# StereoscopicPi.net
KiCad netlist of a schematic drawn in Altium Designer
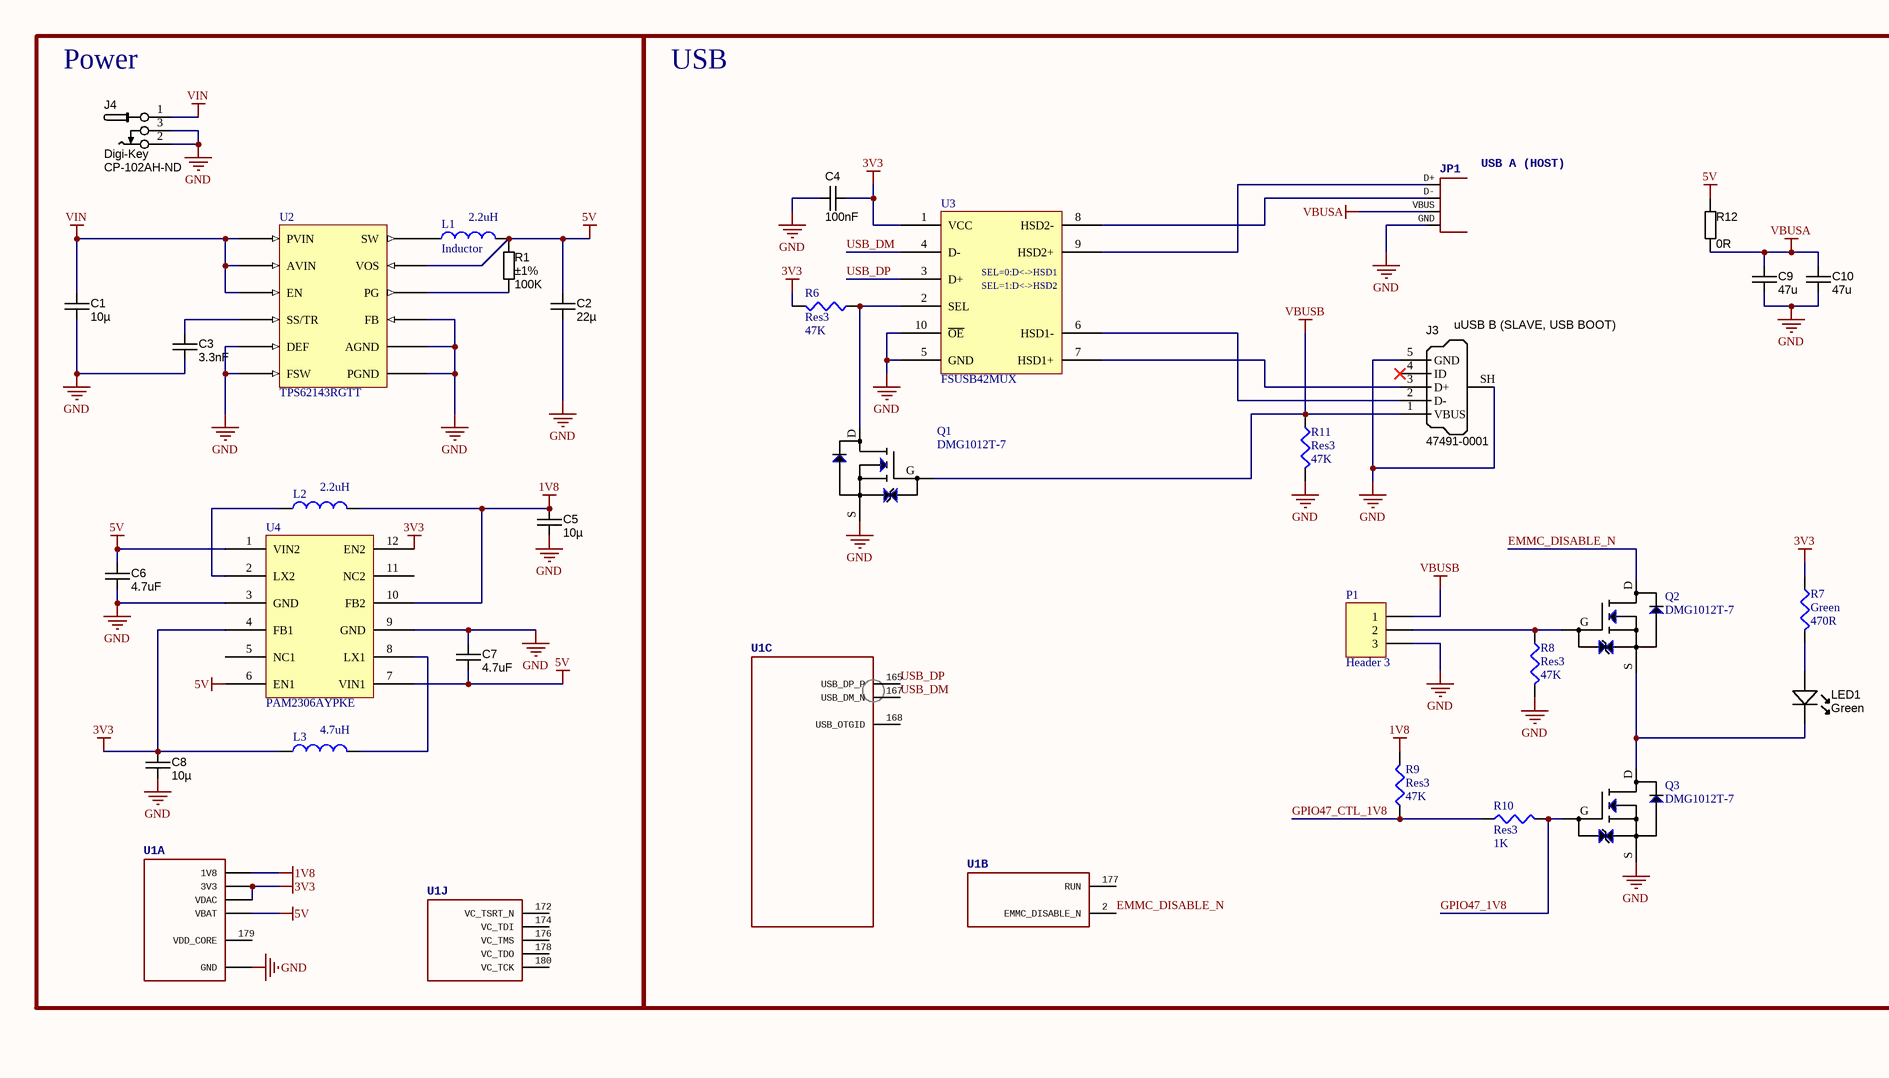
[diagram p0: StereoscopicPi.SchDoc, top left]
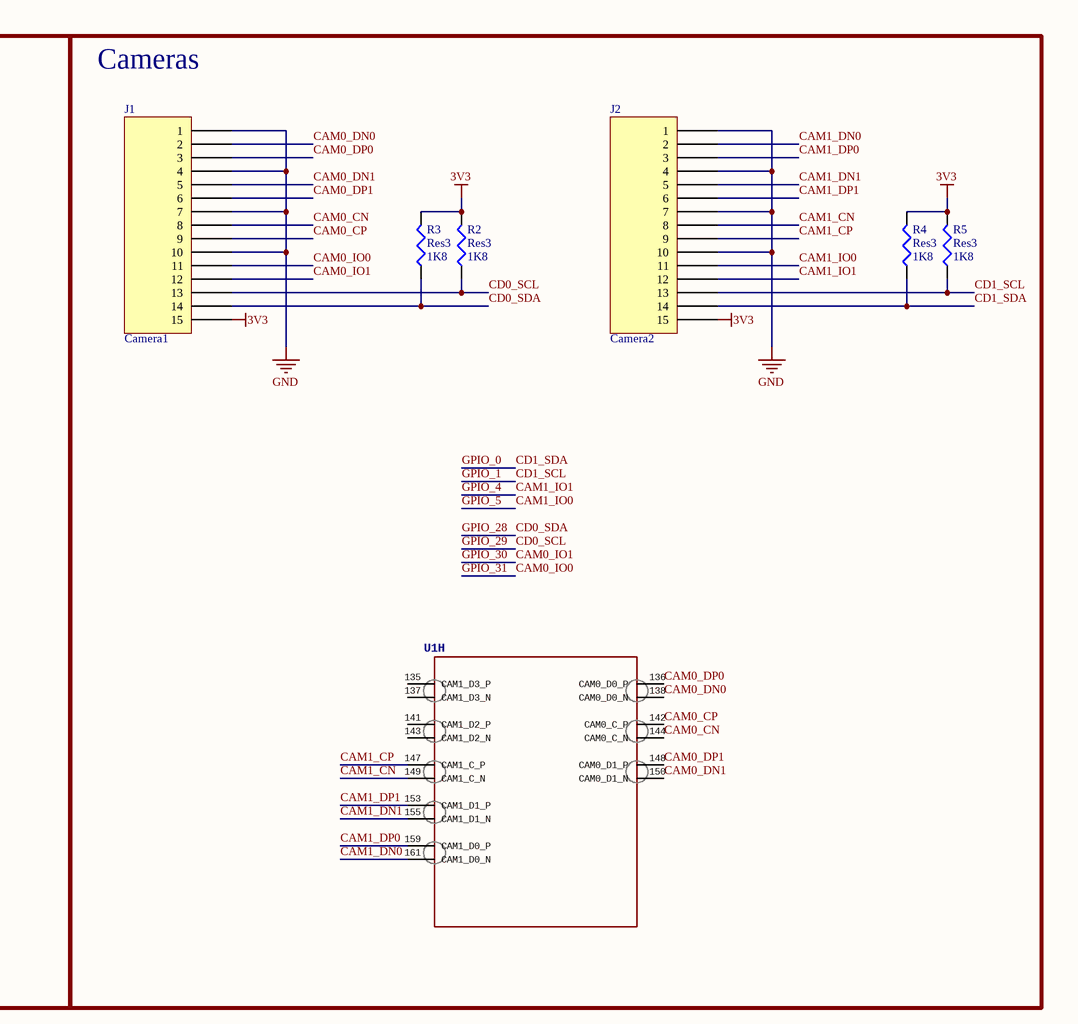
[diagram p1: StereoscopicPi.SchDoc, top right]
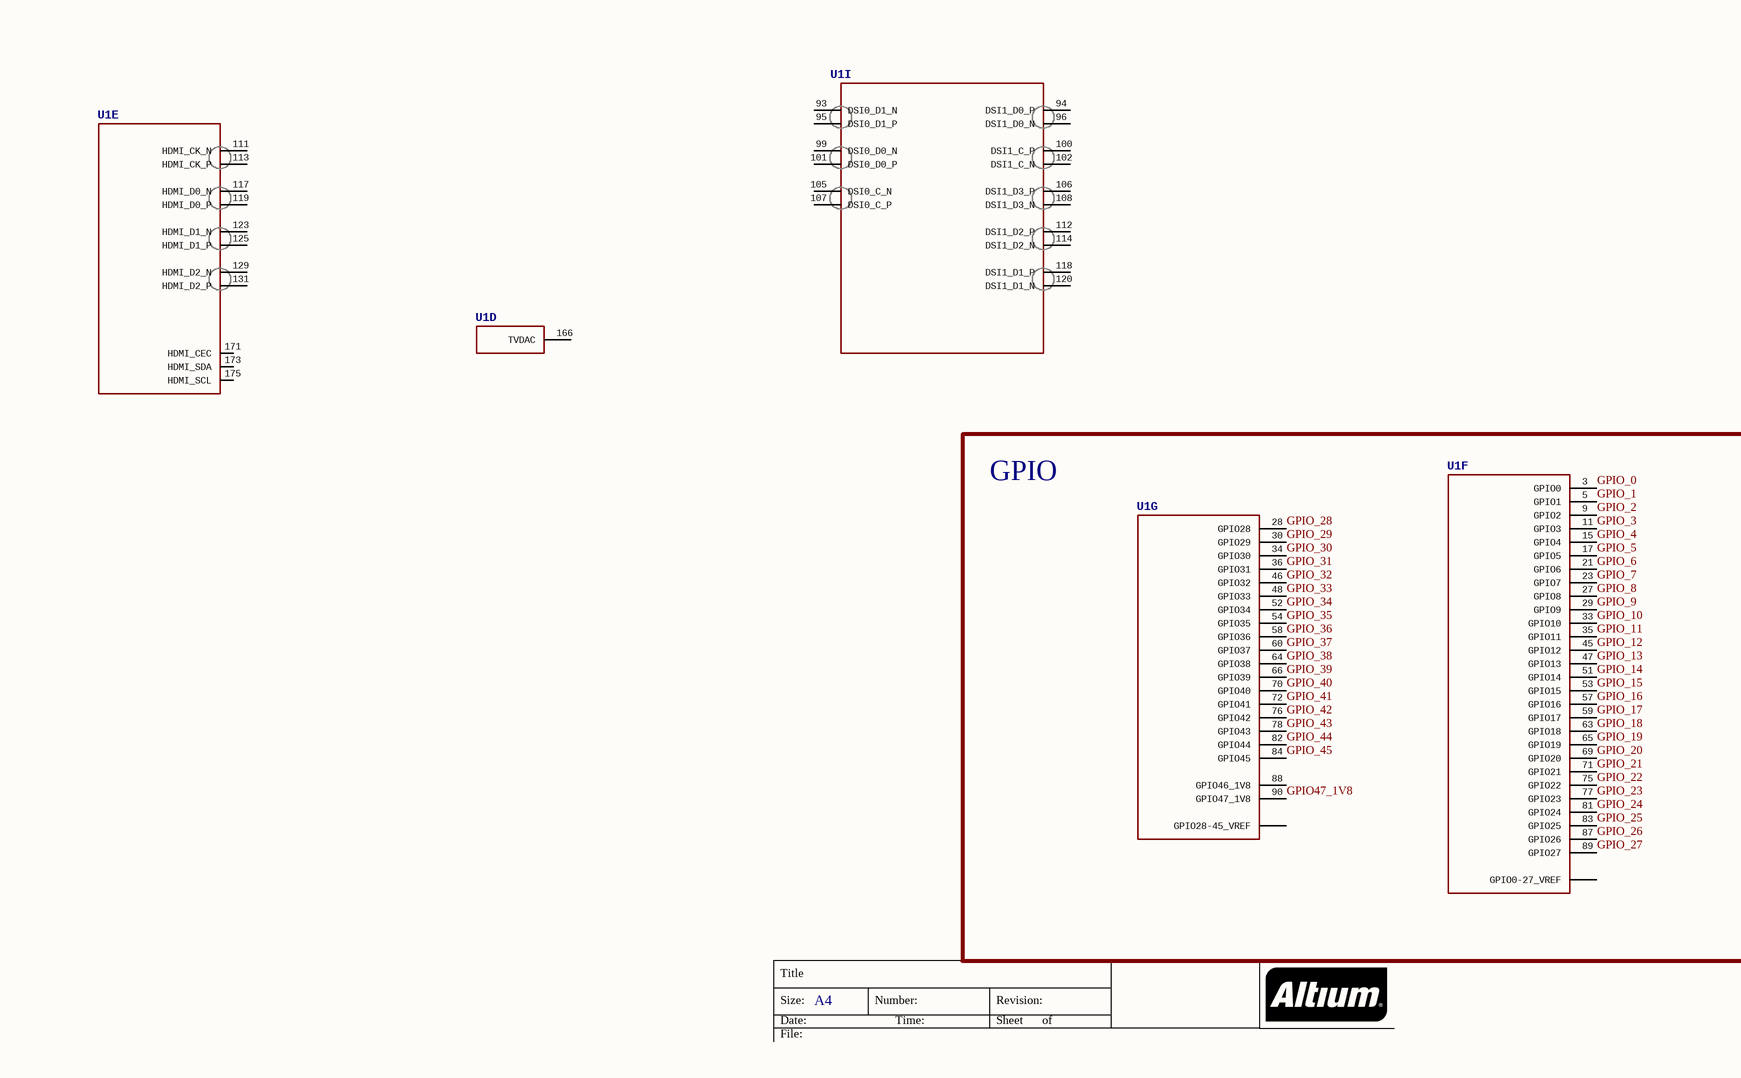
[diagram p2: StereoscopicPi.SchDoc, bottom left]

(export (version "E")
  (design (tool "Eeschema 10.0.6"))
  (components
    (comp (ref "C1")
      (value "10µ")
      (footprint "CAPC3225X220N")
      (description "Capacitor SMD Cer 10uF 20% 16V X5R 1210")
      (fields (field (name "TOLERANCE") "±20%"))
      (libsource (lib "PBL - Capacitors") (part "CAPC_10u_1210_50V"))
    )
    (comp (ref "C2")
      (value "22µ")
      (footprint "CAPC3225X220N")
      (description "Capacitor SMD Cer 22uF 20% 6.3V X5R 1210")
      (fields (field (name "TOLERANCE") "±20%") (field (name "Comment") "approved sub OK"))
      (libsource (lib "PBL - Capacitors") (part "CAPC_22u_1210_6V3_X5R"))
    )
    (comp (ref "C3")
      (value "3.3nF")
      (footprint "CAPC1608X90N")
      (description "Capacitor SMD Cer 10nF 10% 50V X7R 0603")
      (fields (field (name "TOLERANCE") "±10%") (field (name "Comment") "Kemet C0603C332J3RACTU"))
      (libsource (lib "PBL - Capacitors") (part "CAPC_10n_0603_X7R_50V_10%"))
    )
    (comp (ref "C4")
      (value "100nF")
      (footprint "CAPC1608X90N")
      (description "Capacitor SMD Cer 10nF 10% 50V X7R 0603")
      (fields (field (name "TOLERANCE") "±10%"))
      (libsource (lib "PBL - Capacitors") (part "CAPC_10n_0603_X7R_50V_10%"))
    )
    (comp (ref "C5")
      (value "10µ")
      (footprint "CAPC3225X220N")
      (description "Capacitor SMD Cer 10uF 20% 16V X5R 1210")
      (fields (field (name "TOLERANCE") "±20%"))
      (libsource (lib "PBL - Capacitors") (part "CAPC_10u_1210_50V"))
    )
    (comp (ref "C6")
      (value "4.7uF")
      (footprint "CAPC2012X135N")
      (description "Capacitor SMD Cer 4.7uF 10% 16V X5R 0805")
      (fields (field (name "TOLERANCE") "±10%") (field (name "Comment") "approved sub OK"))
      (libsource (lib "PBL - Capacitors") (part "CAPC_4u7_0805"))
    )
    (comp (ref "C7")
      (value "4.7uF")
      (footprint "CAPC2012X135N")
      (description "Capacitor SMD Cer 4.7uF 10% 16V X5R 0805")
      (fields (field (name "TOLERANCE") "±10%") (field (name "Comment") "approved sub OK"))
      (libsource (lib "PBL - Capacitors") (part "CAPC_4u7_0805"))
    )
    (comp (ref "C8")
      (value "10µ")
      (footprint "CAPC3225X220N")
      (description "Capacitor SMD Cer 10uF 20% 16V X5R 1210")
      (fields (field (name "TOLERANCE") "±20%"))
      (libsource (lib "PBL - Capacitors") (part "CAPC_10u_1210_50V"))
    )
    (comp (ref "C9")
      (value "47u")
      (footprint "CAPC3225X220N")
      (description "Capacitor SMD Cer 47uF 10% 10V 1210")
      (fields (field (name "TOLERANCE") "±10%"))
      (libsource (lib "PBL - Capacitors") (part "CAPC_47u_1210_10V_X5R_10%"))
    )
    (comp (ref "C10")
      (value "47u")
      (footprint "CAPC3225X220N")
      (description "Capacitor SMD Cer 47uF 10% 10V 1210")
      (fields (field (name "TOLERANCE") "±10%"))
      (libsource (lib "PBL - Capacitors") (part "CAPC_47u_1210_10V_X5R_10%"))
    )
    (comp (ref "J1")
      (value "Camera1")
      (footprint "SFW15R-2STE1LF")
      (libsource (lib "Schlib1") (part "SFW15R-2STE1LF"))
    )
    (comp (ref "J2")
      (value "Camera2")
      (footprint "SFW15R-2STE1LF")
      (libsource (lib "Schlib1") (part "SFW15R-2STE1LF"))
    )
    (comp (ref "J3")
      (value "uUSB B (SLAVE, USB BOOT)")
      (footprint "USB_Micro-B_Molex_SMD")
      (description "Connector SMD USB Micro Type B middle mount")
      (fields (field (name "MANUFACTURER PART NUMBER 1") "47491-0001"))
      (libsource (lib "PBL - Connectors") (part "USB_Micro_TypeB"))
    )
    (comp (ref "J4")
      (value "CONN_PWR_JACK_2.1x5.5mm")
      (footprint "CONN_PWR_JACK_2.1x5.5mm")
      (description "Power Connector, THT, 2.1mm ID, 5.5mm OD")
      (fields (field (name "SUPPLIER 1") "Digi-Key") (field (name "SUPPLIER PART NUMBER 1") "CP-102AH-ND"))
      (libsource (lib "PBL - Connectors") (part "CONN_PWR_JACK_2.1x5.5mm"))
    )
    (comp (ref "JP1")
      (value "USB A (HOST)")
      (footprint "USB-A-S-NOSILK-FEMALE")
      (libsource (lib "SparkFun-Connectors") (part "USB-A-SMD"))
    )
    (comp (ref "L1")
      (value "Inductor")
      (footprint "IHLP-1212BZ-11")
      (fields (field (name "ALTIUM_VALUE") "2.2uH") (field (name "PUBLISHER") "Altium Limited"))
      (libsource (lib "Miscellaneous Devices") (part "Inductor"))
    )
    (comp (ref "L2")
      (value "2.2uH")
      (footprint "IHLP-1212BZ-11")
      (description "Inductor")
      (fields (field (name "Comment") "IHLP1212BZER2R2M11") (field (name "PUBLISHER") "Altium Limited"))
      (libsource (lib "Miscellaneous Devices") (part "Inductor"))
    )
    (comp (ref "L3")
      (value "4.7uH")
      (footprint "IHLP-2020CZ-11")
      (description "Inductor")
      (fields (field (name "Comment") "IHLP2020CZER4R7M11") (field (name "PUBLISHER") "Altium Limited"))
      (libsource (lib "Miscellaneous Devices") (part "Inductor"))
    )
    (comp (ref "LED1")
      (value "Green")
      (footprint "LED-0603-GREEN")
      (description "LED 0603 SMD Green 570nm 50mcd 20mA")
      (libsource (lib "PBL - Light Sources") (part "LED_SMD_Green_0603_570nm"))
    )
    (comp (ref "P1")
      (value "Header 3")
      (footprint "HDR1X3")
      (description "Header, 3-Pin")
      (fields (field (name "PUBLISHER") "Altium Limited"))
      (libsource (lib "Miscellaneous Connectors") (part "Header 3"))
    )
    (comp (ref "Q1")
      (value "DMG1012T-7")
      (footprint "DMG1012T-7")
      (libsource (lib "Schlib1") (part "DMG1012T-7"))
    )
    (comp (ref "Q2")
      (value "DMG1012T-7")
      (footprint "DMG1012T-7")
      (libsource (lib "Schlib1") (part "DMG1012T-7"))
    )
    (comp (ref "Q3")
      (value "DMG1012T-7")
      (footprint "DMG1012T-7")
      (libsource (lib "Schlib1") (part "DMG1012T-7"))
    )
    (comp (ref "R1")
      (value "100K")
      (footprint "RESC1608X55N")
      (description "Resistor SMD chip 100k Ohm 0.1W 1% 0603")
      (fields (field (name "TOLERANCE") "±1%") (field (name "Comment") "Thick Film"))
      (libsource (lib "PBL - Resistors") (part "RES_100K_0603_1%"))
    )
    (comp (ref "R2")
      (value "Res3")
      (footprint "J1-0603")
      (description "Resistor")
      (fields (field (name "ALTIUM_VALUE") "1K8") (field (name "PUBLISHER") "Altium Limited"))
      (libsource (lib "Miscellaneous Devices") (part "Res3"))
    )
    (comp (ref "R3")
      (value "Res3")
      (footprint "J1-0603")
      (description "Resistor")
      (fields (field (name "ALTIUM_VALUE") "1K8") (field (name "PUBLISHER") "Altium Limited"))
      (libsource (lib "Miscellaneous Devices") (part "Res3"))
    )
    (comp (ref "R4")
      (value "Res3")
      (footprint "J1-0603")
      (description "Resistor")
      (fields (field (name "ALTIUM_VALUE") "1K8") (field (name "PUBLISHER") "Altium Limited"))
      (libsource (lib "Miscellaneous Devices") (part "Res3"))
    )
    (comp (ref "R5")
      (value "Res3")
      (footprint "J1-0603")
      (description "Resistor")
      (fields (field (name "ALTIUM_VALUE") "1K8") (field (name "PUBLISHER") "Altium Limited"))
      (libsource (lib "Miscellaneous Devices") (part "Res3"))
    )
    (comp (ref "R6")
      (value "Res3")
      (footprint "J1-0603")
      (description "Resistor")
      (fields (field (name "ALTIUM_VALUE") "47K") (field (name "PUBLISHER") "Altium Limited"))
      (libsource (lib "Miscellaneous Devices") (part "Res3"))
    )
    (comp (ref "R7")
      (value "Green")
      (footprint "J1-0603")
      (description "Resistor")
      (fields (field (name "ALTIUM_VALUE") "470R") (field (name "PUBLISHER") "Altium Limited"))
      (libsource (lib "Miscellaneous Devices") (part "Res3"))
    )
    (comp (ref "R8")
      (value "Res3")
      (footprint "J1-0603")
      (description "Resistor")
      (fields (field (name "ALTIUM_VALUE") "47K") (field (name "PUBLISHER") "Altium Limited"))
      (libsource (lib "Miscellaneous Devices") (part "Res3"))
    )
    (comp (ref "R9")
      (value "Res3")
      (footprint "J1-0603")
      (description "Resistor")
      (fields (field (name "ALTIUM_VALUE") "47K") (field (name "PUBLISHER") "Altium Limited"))
      (libsource (lib "Miscellaneous Devices") (part "Res3"))
    )
    (comp (ref "R10")
      (value "Res3")
      (footprint "J1-0603")
      (description "Resistor")
      (fields (field (name "ALTIUM_VALUE") "1K") (field (name "PUBLISHER") "Altium Limited"))
      (libsource (lib "Miscellaneous Devices") (part "Res3"))
    )
    (comp (ref "R11")
      (value "Res3")
      (footprint "J1-0603")
      (description "Resistor")
      (fields (field (name "ALTIUM_VALUE") "47K") (field (name "PUBLISHER") "Altium Limited"))
      (libsource (lib "Miscellaneous Devices") (part "Res3"))
    )
    (comp (ref "R12")
      (value "0R")
      (footprint "RESC1608X55N")
      (description "Resistor SMD chip 100k Ohm 0.1W 1% 0603")
      (fields (field (name "TOLERANCE") "±1%") (field (name "Comment") "Thick Film"))
      (libsource (lib "PBL - Resistors") (part "RES_100K_0603_1%"))
    )
    (comp (ref "U1")
      (value "Raspberry Pi Compute Module As anounced in this blog post  http://www.raspberrypi.org/raspberry-pi-compute-module-new-product/  Based on infomation from this schematic http://www.raspberrypi.org/wp-content/uploads/2014/04/RPI-CM-V1_1-SCHEMATIC.pdf  Footprint is unproven and no matching part confimed as of yet")
      (footprint "1-1376408-4")
      (libsource (lib "Ciseco Pi Compute Module") (part "RASPBERRY_PI_CM-1-1376408-4"))
    )
    (comp (ref "U2")
      (value "TPS62143RGTT")
      (footprint "QFN50P300X300X100_HS-17M")
      (libsource (lib "Schlib1") (part "TPS62143 5V 2A LDO SMPS Buck"))
    )
    (comp (ref "U3")
      (value "FSUSB42MUX")
      (footprint "FSUSB42MUX")
      (libsource (lib "Schlib1") (part "FSUSB42MUX"))
    )
    (comp (ref "U4")
      (value "PAM2306AYPKE")
      (footprint "PAM2306")
      (libsource (lib "Schlib1") (part "PAM2306"))
    )
  )
  (nets
    (net (code "1") (name "/CAM0_CN") (class "Default")
      (node (ref "J1") (pin "8") (pinfunction "8_8") (pintype "passive"))
      (node (ref "U1") (pin "144") (pinfunction "CAM0_C_N_144") (pintype "passive"))
    )
    (net (code "2") (name "/CAM0_CP") (class "Default")
      (node (ref "J1") (pin "9") (pinfunction "9_9") (pintype "passive"))
      (node (ref "U1") (pin "142") (pinfunction "CAM0_C_P_142") (pintype "passive"))
    )
    (net (code "3") (name "/CAM0_DN0") (class "Default")
      (node (ref "J1") (pin "2") (pinfunction "2_2") (pintype "passive"))
      (node (ref "U1") (pin "138") (pinfunction "CAM0_D0_N_138") (pintype "passive"))
    )
    (net (code "4") (name "/CAM0_DN1") (class "Default")
      (node (ref "J1") (pin "5") (pinfunction "5_5") (pintype "passive"))
      (node (ref "U1") (pin "150") (pinfunction "CAM0_D1_N_150") (pintype "passive"))
    )
    (net (code "5") (name "/CAM0_DP0") (class "Default")
      (node (ref "J1") (pin "3") (pinfunction "3_3") (pintype "passive"))
      (node (ref "U1") (pin "136") (pinfunction "CAM0_D0_P_136") (pintype "passive"))
    )
    (net (code "6") (name "/CAM0_DP1") (class "Default")
      (node (ref "J1") (pin "6") (pinfunction "6_6") (pintype "passive"))
      (node (ref "U1") (pin "148") (pinfunction "CAM0_D1_P_148") (pintype "passive"))
    )
    (net (code "7") (name "/CAM0_IO0") (class "Default")
      (node (ref "J1") (pin "11") (pinfunction "11_11") (pintype "passive"))
      (node (ref "U1") (pin "36") (pinfunction "GPIO31_36") (pintype "passive"))
    )
    (net (code "8") (name "/CAM0_IO1") (class "Default")
      (node (ref "J1") (pin "12") (pinfunction "12_12") (pintype "passive"))
      (node (ref "U1") (pin "34") (pinfunction "GPIO30_34") (pintype "passive"))
    )
    (net (code "9") (name "/CAM1_CN") (class "Default")
      (node (ref "J2") (pin "8") (pinfunction "8_8") (pintype "passive"))
      (node (ref "U1") (pin "149") (pinfunction "CAM1_C_N_149") (pintype "passive"))
    )
    (net (code "10") (name "/CAM1_CP") (class "Default")
      (node (ref "J2") (pin "9") (pinfunction "9_9") (pintype "passive"))
      (node (ref "U1") (pin "147") (pinfunction "CAM1_C_P_147") (pintype "passive"))
    )
    (net (code "11") (name "/CAM1_DN0") (class "Default")
      (node (ref "J2") (pin "2") (pinfunction "2_2") (pintype "passive"))
      (node (ref "U1") (pin "161") (pinfunction "CAM1_D0_N_161") (pintype "passive"))
    )
    (net (code "12") (name "/CAM1_DN1") (class "Default")
      (node (ref "J2") (pin "5") (pinfunction "5_5") (pintype "passive"))
      (node (ref "U1") (pin "155") (pinfunction "CAM1_D1_N_155") (pintype "passive"))
    )
    (net (code "13") (name "/CAM1_DP0") (class "Default")
      (node (ref "J2") (pin "3") (pinfunction "3_3") (pintype "passive"))
      (node (ref "U1") (pin "159") (pinfunction "CAM1_D0_P_159") (pintype "passive"))
    )
    (net (code "14") (name "/CAM1_DP1") (class "Default")
      (node (ref "J2") (pin "6") (pinfunction "6_6") (pintype "passive"))
      (node (ref "U1") (pin "153") (pinfunction "CAM1_D1_P_153") (pintype "passive"))
    )
    (net (code "15") (name "/CAM1_IO0") (class "Default")
      (node (ref "J2") (pin "11") (pinfunction "11_11") (pintype "passive"))
      (node (ref "U1") (pin "17") (pinfunction "GPIO5_17") (pintype "passive"))
    )
    (net (code "16") (name "/CAM1_IO1") (class "Default")
      (node (ref "J2") (pin "12") (pinfunction "12_12") (pintype "passive"))
      (node (ref "U1") (pin "15") (pinfunction "GPIO4_15") (pintype "passive"))
    )
    (net (code "17") (name "/CD0_SCL") (class "Default")
      (node (ref "J1") (pin "13") (pinfunction "13_13") (pintype "passive"))
      (node (ref "R2") (pin "1") (pinfunction "1_1") (pintype "passive"))
      (node (ref "U1") (pin "30") (pinfunction "GPIO29_30") (pintype "passive"))
    )
    (net (code "18") (name "/CD0_SDA") (class "Default")
      (node (ref "J1") (pin "14") (pinfunction "14_14") (pintype "passive"))
      (node (ref "R3") (pin "1") (pinfunction "1_1") (pintype "passive"))
      (node (ref "U1") (pin "28") (pinfunction "GPIO28_28") (pintype "passive"))
    )
    (net (code "19") (name "/CD1_SCL") (class "Default")
      (node (ref "J2") (pin "13") (pinfunction "13_13") (pintype "passive"))
      (node (ref "R5") (pin "1") (pinfunction "1_1") (pintype "passive"))
      (node (ref "U1") (pin "5") (pinfunction "GPIO1_5") (pintype "passive"))
    )
    (net (code "20") (name "/CD1_SDA") (class "Default")
      (node (ref "J2") (pin "14") (pinfunction "14_14") (pintype "passive"))
      (node (ref "R4") (pin "1") (pinfunction "1_1") (pintype "passive"))
      (node (ref "U1") (pin "3") (pinfunction "GPIO0_3") (pintype "passive"))
    )
    (net (code "21") (name "/EMMC_DISABLE_N") (class "Default")
      (node (ref "Q2") (pin "D") (pinfunction "D_D") (pintype "passive"))
      (node (ref "U1") (pin "2") (pinfunction "EMMC_DISABLE_N_2") (pintype "passive"))
    )
    (net (code "22") (name "/GPIO47_1V8") (class "Default")
      (node (ref "Q3") (pin "G") (pinfunction "G_G") (pintype "passive"))
      (node (ref "R10") (pin "2") (pinfunction "2_2") (pintype "passive"))
      (node (ref "U1") (pin "90") (pinfunction "GPIO47_1V8_90") (pintype "passive"))
    )
    (net (code "23") (name "/GPIO47_CTL_1V8") (class "Default")
      (node (ref "R10") (pin "1") (pinfunction "1_1") (pintype "passive"))
      (node (ref "R9") (pin "1") (pinfunction "1_1") (pintype "passive"))
    )
    (net (code "24") (name "/GPIO_2") (class "Default")
      (node (ref "U1") (pin "9") (pinfunction "GPIO2_9") (pintype "passive"))
    )
    (net (code "25") (name "/GPIO_3") (class "Default")
      (node (ref "U1") (pin "11") (pinfunction "GPIO3_11") (pintype "passive"))
    )
    (net (code "26") (name "/GPIO_6") (class "Default")
      (node (ref "U1") (pin "21") (pinfunction "GPIO6_21") (pintype "passive"))
    )
    (net (code "27") (name "/GPIO_7") (class "Default")
      (node (ref "U1") (pin "23") (pinfunction "GPIO7_23") (pintype "passive"))
    )
    (net (code "28") (name "/GPIO_8") (class "Default")
      (node (ref "U1") (pin "27") (pinfunction "GPIO8_27") (pintype "passive"))
    )
    (net (code "29") (name "/GPIO_9") (class "Default")
      (node (ref "U1") (pin "29") (pinfunction "GPIO9_29") (pintype "passive"))
    )
    (net (code "30") (name "/GPIO_10") (class "Default")
      (node (ref "U1") (pin "33") (pinfunction "GPIO10_33") (pintype "passive"))
    )
    (net (code "31") (name "/GPIO_11") (class "Default")
      (node (ref "U1") (pin "35") (pinfunction "GPIO11_35") (pintype "passive"))
    )
    (net (code "32") (name "/GPIO_12") (class "Default")
      (node (ref "U1") (pin "45") (pinfunction "GPIO12_45") (pintype "passive"))
    )
    (net (code "33") (name "/GPIO_13") (class "Default")
      (node (ref "U1") (pin "47") (pinfunction "GPIO13_47") (pintype "passive"))
    )
    (net (code "34") (name "/GPIO_14") (class "Default")
      (node (ref "U1") (pin "51") (pinfunction "GPIO14_51") (pintype "passive"))
    )
    (net (code "35") (name "/GPIO_15") (class "Default")
      (node (ref "U1") (pin "53") (pinfunction "GPIO15_53") (pintype "passive"))
    )
    (net (code "36") (name "/GPIO_16") (class "Default")
      (node (ref "U1") (pin "57") (pinfunction "GPIO16_57") (pintype "passive"))
    )
    (net (code "37") (name "/GPIO_17") (class "Default")
      (node (ref "U1") (pin "59") (pinfunction "GPIO17_59") (pintype "passive"))
    )
    (net (code "38") (name "/GPIO_18") (class "Default")
      (node (ref "U1") (pin "63") (pinfunction "GPIO18_63") (pintype "passive"))
    )
    (net (code "39") (name "/GPIO_19") (class "Default")
      (node (ref "U1") (pin "65") (pinfunction "GPIO19_65") (pintype "passive"))
    )
    (net (code "40") (name "/GPIO_20") (class "Default")
      (node (ref "U1") (pin "69") (pinfunction "GPIO20_69") (pintype "passive"))
    )
    (net (code "41") (name "/GPIO_21") (class "Default")
      (node (ref "U1") (pin "71") (pinfunction "GPIO21_71") (pintype "passive"))
    )
    (net (code "42") (name "/GPIO_22") (class "Default")
      (node (ref "U1") (pin "75") (pinfunction "GPIO22_75") (pintype "passive"))
    )
    (net (code "43") (name "/GPIO_23") (class "Default")
      (node (ref "U1") (pin "77") (pinfunction "GPIO23_77") (pintype "passive"))
    )
    (net (code "44") (name "/GPIO_24") (class "Default")
      (node (ref "U1") (pin "81") (pinfunction "GPIO24_81") (pintype "passive"))
    )
    (net (code "45") (name "/GPIO_25") (class "Default")
      (node (ref "U1") (pin "83") (pinfunction "GPIO25_83") (pintype "passive"))
    )
    (net (code "46") (name "/GPIO_26") (class "Default")
      (node (ref "U1") (pin "87") (pinfunction "GPIO26_87") (pintype "passive"))
    )
    (net (code "47") (name "/GPIO_27") (class "Default")
      (node (ref "U1") (pin "89") (pinfunction "GPIO27_89") (pintype "passive"))
    )
    (net (code "48") (name "/GPIO_32") (class "Default")
      (node (ref "U1") (pin "46") (pinfunction "GPIO32_46") (pintype "passive"))
    )
    (net (code "49") (name "/GPIO_33") (class "Default")
      (node (ref "U1") (pin "48") (pinfunction "GPIO33_48") (pintype "passive"))
    )
    (net (code "50") (name "/GPIO_34") (class "Default")
      (node (ref "U1") (pin "52") (pinfunction "GPIO34_52") (pintype "passive"))
    )
    (net (code "51") (name "/GPIO_35") (class "Default")
      (node (ref "U1") (pin "54") (pinfunction "GPIO35_54") (pintype "passive"))
    )
    (net (code "52") (name "/GPIO_36") (class "Default")
      (node (ref "U1") (pin "58") (pinfunction "GPIO36_58") (pintype "passive"))
    )
    (net (code "53") (name "/GPIO_37") (class "Default")
      (node (ref "U1") (pin "60") (pinfunction "GPIO37_60") (pintype "passive"))
    )
    (net (code "54") (name "/GPIO_38") (class "Default")
      (node (ref "U1") (pin "64") (pinfunction "GPIO38_64") (pintype "passive"))
    )
    (net (code "55") (name "/GPIO_39") (class "Default")
      (node (ref "U1") (pin "66") (pinfunction "GPIO39_66") (pintype "passive"))
    )
    (net (code "56") (name "/GPIO_40") (class "Default")
      (node (ref "U1") (pin "70") (pinfunction "GPIO40_70") (pintype "passive"))
    )
    (net (code "57") (name "/GPIO_41") (class "Default")
      (node (ref "U1") (pin "72") (pinfunction "GPIO41_72") (pintype "passive"))
    )
    (net (code "58") (name "/GPIO_42") (class "Default")
      (node (ref "U1") (pin "76") (pinfunction "GPIO42_76") (pintype "passive"))
    )
    (net (code "59") (name "/GPIO_43") (class "Default")
      (node (ref "U1") (pin "78") (pinfunction "GPIO43_78") (pintype "passive"))
    )
    (net (code "60") (name "/GPIO_44") (class "Default")
      (node (ref "U1") (pin "82") (pinfunction "GPIO44_82") (pintype "passive"))
    )
    (net (code "61") (name "/GPIO_45") (class "Default")
      (node (ref "U1") (pin "84") (pinfunction "GPIO45_84") (pintype "passive"))
    )
    (net (code "62") (name "/USB_DM") (class "Default")
      (node (ref "U1") (pin "167") (pinfunction "USB_DM_N_167") (pintype "passive"))
      (node (ref "U3") (pin "4") (pinfunction "D-_4") (pintype "passive"))
    )
    (net (code "63") (name "/USB_DP") (class "Default")
      (node (ref "U1") (pin "165") (pinfunction "USB_DP_P_165") (pintype "passive"))
      (node (ref "U3") (pin "3") (pinfunction "D+_3") (pintype "passive"))
    )
    (net (code "64") (name "1V8") (class "Default")
      (node (ref "C5") (pin "1") (pintype "passive"))
      (node (ref "L2") (pin "1") (pinfunction "2_1") (pintype "passive"))
      (node (ref "R9") (pin "2") (pinfunction "2_2") (pintype "passive"))
      (node (ref "U1") (pin "1V8") (pinfunction "1V8_1V8") (pintype "passive"))
      (node (ref "U4") (pin "10") (pinfunction "FB2_10") (pintype "passive"))
    )
    (net (code "65") (name "3V3") (class "Default")
      (node (ref "C4") (pin "2") (pintype "passive"))
      (node (ref "C8") (pin "1") (pintype "passive"))
      (node (ref "J1") (pin "15") (pinfunction "15_15") (pintype "passive"))
      (node (ref "J2") (pin "15") (pinfunction "15_15") (pintype "passive"))
      (node (ref "L3") (pin "0") (pinfunction "1_0") (pintype "passive"))
      (node (ref "R2") (pin "2") (pinfunction "2_2") (pintype "passive"))
      (node (ref "R3") (pin "2") (pinfunction "2_2") (pintype "passive"))
      (node (ref "R4") (pin "2") (pinfunction "2_2") (pintype "passive"))
      (node (ref "R5") (pin "2") (pinfunction "2_2") (pintype "passive"))
      (node (ref "R6") (pin "2") (pinfunction "2_2") (pintype "passive"))
      (node (ref "R7") (pin "1") (pinfunction "1_1") (pintype "passive"))
      (node (ref "U1") (pin "3V3") (pinfunction "3V3_3V3") (pintype "passive"))
      (node (ref "U1") (pin "VDAC") (pinfunction "VDAC_VDAC") (pintype "passive"))
      (node (ref "U3") (pin "1") (pinfunction "VCC_1") (pintype "passive"))
      (node (ref "U4") (pin "12") (pinfunction "EN2_12") (pintype "passive"))
      (node (ref "U4") (pin "4") (pinfunction "FB1_4") (pintype "passive"))
    )
    (net (code "66") (name "5V") (class "Default")
      (node (ref "C2") (pin "1") (pintype "passive"))
      (node (ref "C6") (pin "1") (pintype "passive"))
      (node (ref "C7") (pin "2") (pintype "passive"))
      (node (ref "L1") (pin "1") (pinfunction "2_1") (pintype "passive"))
      (node (ref "R1") (pin "1") (pinfunction "1_1") (pintype "passive"))
      (node (ref "R12") (pin "1") (pinfunction "1_1") (pintype "passive"))
      (node (ref "U1") (pin "VBAT") (pinfunction "VBAT_VBAT") (pintype "passive"))
      (node (ref "U2") (pin "14") (pinfunction "VOS_14") (pintype "input"))
      (node (ref "U4") (pin "1") (pinfunction "VIN2_1") (pintype "passive"))
      (node (ref "U4") (pin "6") (pinfunction "EN1_6") (pintype "passive"))
      (node (ref "U4") (pin "7") (pinfunction "VIN1_7") (pintype "passive"))
    )
    (net (code "67") (name "GND") (class "Default")
      (node (ref "C1") (pin "2") (pintype "passive"))
      (node (ref "C10") (pin "2") (pintype "passive"))
      (node (ref "C2") (pin "2") (pintype "passive"))
      (node (ref "C3") (pin "2") (pintype "passive"))
      (node (ref "C4") (pin "1") (pintype "passive"))
      (node (ref "C5") (pin "2") (pintype "passive"))
      (node (ref "C6") (pin "2") (pintype "passive"))
      (node (ref "C7") (pin "1") (pintype "passive"))
      (node (ref "C8") (pin "2") (pintype "passive"))
      (node (ref "C9") (pin "2") (pintype "passive"))
      (node (ref "J1") (pin "1") (pinfunction "1_1") (pintype "passive"))
      (node (ref "J1") (pin "10") (pinfunction "10_10") (pintype "passive"))
      (node (ref "J1") (pin "4") (pinfunction "4_4") (pintype "passive"))
      (node (ref "J1") (pin "7") (pinfunction "7_7") (pintype "passive"))
      (node (ref "J2") (pin "1") (pinfunction "1_1") (pintype "passive"))
      (node (ref "J2") (pin "10") (pinfunction "10_10") (pintype "passive"))
      (node (ref "J2") (pin "4") (pinfunction "4_4") (pintype "passive"))
      (node (ref "J2") (pin "7") (pinfunction "7_7") (pintype "passive"))
      (node (ref "J3") (pin "5") (pinfunction "GND_5") (pintype "passive"))
      (node (ref "J3") (pin "SH") (pinfunction "Shell_SH") (pintype "passive"))
      (node (ref "J4") (pin "2") (pinfunction "2_2") (pintype "passive"))
      (node (ref "J4") (pin "3") (pinfunction "3_3") (pintype "passive"))
      (node (ref "JP1") (pin "GND") (pinfunction "GND_GND") (pintype "passive"))
      (node (ref "P1") (pin "3") (pinfunction "3_3") (pintype "passive"))
      (node (ref "Q1") (pin "S") (pinfunction "3_S") (pintype "passive"))
      (node (ref "Q3") (pin "S") (pinfunction "3_S") (pintype "passive"))
      (node (ref "R11") (pin "2") (pinfunction "2_2") (pintype "passive"))
      (node (ref "R8") (pin "2") (pinfunction "2_2") (pintype "passive"))
      (node (ref "U1") (pin "GND") (pinfunction "GND_GND") (pintype "passive"))
      (node (ref "U2") (pin "15") (pinfunction "PGND_15") (pintype "passive"))
      (node (ref "U2") (pin "5") (pinfunction "FB_5") (pintype "input"))
      (node (ref "U2") (pin "6") (pinfunction "AGND_6") (pintype "passive"))
      (node (ref "U2") (pin "7") (pinfunction "FSW_7") (pintype "input"))
      (node (ref "U2") (pin "8") (pinfunction "DEF_8") (pintype "input"))
      (node (ref "U3") (pin "10") (pinfunction "~{OE}_10") (pintype "passive"))
      (node (ref "U3") (pin "5") (pinfunction "GND_5") (pintype "passive"))
      (node (ref "U4") (pin "3") (pinfunction "GND_3") (pintype "passive"))
      (node (ref "U4") (pin "9") (pinfunction "GND_9") (pintype "passive"))
    )
    (net (code "68") (name "Net-(J3-D+)") (class "Default")
      (node (ref "J3") (pin "3") (pinfunction "D+_3") (pintype "passive"))
      (node (ref "U3") (pin "7") (pinfunction "HSD1+_7") (pintype "passive"))
    )
    (net (code "69") (name "Net-(J3-D-)") (class "Default")
      (node (ref "J3") (pin "2") (pinfunction "D-_2") (pintype "passive"))
      (node (ref "U3") (pin "6") (pinfunction "HSD1-_6") (pintype "passive"))
    )
    (net (code "70") (name "Net-(L1-1)") (class "Default")
      (node (ref "L1") (pin "0") (pinfunction "1_0") (pintype "passive"))
      (node (ref "U2") (pin "1") (pinfunction "SW_1") (pintype "output"))
    )
    (net (code "71") (name "Net-(L2-1)") (class "Default")
      (node (ref "L2") (pin "0") (pinfunction "1_0") (pintype "passive"))
      (node (ref "U4") (pin "2") (pinfunction "LX2_2") (pintype "passive"))
    )
    (net (code "72") (name "Net-(L3-2)") (class "Default")
      (node (ref "L3") (pin "1") (pinfunction "2_1") (pintype "passive"))
      (node (ref "U4") (pin "8") (pinfunction "LX1_8") (pintype "passive"))
    )
    (net (code "73") (name "Net-(LED1-PadA)") (class "Default")
      (node (ref "LED1") (pin "A") (pinfunction "A_A") (pintype "passive"))
      (node (ref "R7") (pin "2") (pinfunction "2_2") (pintype "passive"))
    )
    (net (code "74") (name "Net-(P1-Pad2)") (class "Default")
      (node (ref "P1") (pin "2") (pinfunction "2_2") (pintype "passive"))
      (node (ref "Q2") (pin "G") (pinfunction "G_G") (pintype "passive"))
      (node (ref "R8") (pin "1") (pinfunction "1_1") (pintype "passive"))
    )
    (net (code "75") (name "Net-(Q2-3)") (class "Default")
      (node (ref "LED1") (pin "K") (pinfunction "K_K") (pintype "passive"))
      (node (ref "Q2") (pin "S") (pinfunction "3_S") (pintype "passive"))
      (node (ref "Q3") (pin "D") (pinfunction "D_D") (pintype "passive"))
    )
    (net (code "76") (name "Net-(U2-PG)") (class "Default")
      (node (ref "R1") (pin "2") (pinfunction "2_2") (pintype "passive"))
      (node (ref "U2") (pin "4") (pinfunction "PG_4") (pintype "output"))
    )
    (net (code "77") (name "Net-(U2-SS{slash}TR)") (class "Default")
      (node (ref "C3") (pin "1") (pintype "passive"))
      (node (ref "U2") (pin "9") (pinfunction "SS/TR_9") (pintype "input"))
    )
    (net (code "78") (name "Net-(U3-HSD2+)") (class "Default")
      (node (ref "JP1") (pin "D+") (pinfunction "D+_D+") (pintype "passive"))
      (node (ref "U3") (pin "9") (pinfunction "HSD2+_9") (pintype "passive"))
    )
    (net (code "79") (name "Net-(U3-HSD2-)") (class "Default")
      (node (ref "JP1") (pin "D-") (pinfunction "D-_D-") (pintype "passive"))
      (node (ref "U3") (pin "8") (pinfunction "HSD2-_8") (pintype "passive"))
    )
    (net (code "80") (name "Net-(U3-SEL)") (class "Default")
      (node (ref "Q1") (pin "D") (pinfunction "D_D") (pintype "passive"))
      (node (ref "R6") (pin "1") (pinfunction "1_1") (pintype "passive"))
      (node (ref "U3") (pin "2") (pinfunction "SEL_2") (pintype "passive"))
    )
    (net (code "81") (name "VBUSA") (class "Default")
      (node (ref "C10") (pin "1") (pintype "passive"))
      (node (ref "C9") (pin "1") (pintype "passive"))
      (node (ref "JP1") (pin "VBUS") (pinfunction "VBUS_VBUS") (pintype "passive"))
      (node (ref "R12") (pin "2") (pinfunction "2_2") (pintype "passive"))
    )
    (net (code "82") (name "VBUSB") (class "Default")
      (node (ref "J3") (pin "1") (pinfunction "VBUS_1") (pintype "passive"))
      (node (ref "P1") (pin "1") (pinfunction "1_1") (pintype "passive"))
      (node (ref "Q1") (pin "G") (pinfunction "G_G") (pintype "passive"))
      (node (ref "R11") (pin "1") (pinfunction "1_1") (pintype "passive"))
    )
    (net (code "83") (name "VIN") (class "Default")
      (node (ref "C1") (pin "1") (pintype "passive"))
      (node (ref "J4") (pin "1") (pinfunction "1_1") (pintype "passive"))
      (node (ref "U2") (pin "10") (pinfunction "AVIN_10") (pintype "input"))
      (node (ref "U2") (pin "11") (pinfunction "PVIN_11") (pintype "input"))
      (node (ref "U2") (pin "13") (pinfunction "EN_13") (pintype "input"))
    )
    (net (code "84") (name "unconnected-(J3-ID-Pad4)") (class "Default")
      (node (ref "J3") (pin "4") (pinfunction "ID_4") (pintype "passive+no_connect"))
    )
    (net (code "85") (name "unconnected-(U1A-VDD_CORE-Pad179)") (class "Default")
      (node (ref "U1") (pin "179") (pinfunction "VDD_CORE_179") (pintype "passive"))
    )
    (net (code "86") (name "unconnected-(U1B-RUN-Pad177)") (class "Default")
      (node (ref "U1") (pin "177") (pinfunction "RUN_177") (pintype "passive"))
    )
    (net (code "87") (name "unconnected-(U1C-USB_OTGID-Pad168)") (class "Default")
      (node (ref "U1") (pin "168") (pinfunction "USB_OTGID_168") (pintype "passive"))
    )
    (net (code "88") (name "unconnected-(U1D-TVDAC-Pad166)") (class "Default")
      (node (ref "U1") (pin "166") (pinfunction "TVDAC_166") (pintype "passive"))
    )
    (net (code "89") (name "unconnected-(U1E-HDMI_CEC-Pad171)") (class "Default")
      (node (ref "U1") (pin "171") (pinfunction "HDMI_CEC_171") (pintype "passive"))
    )
    (net (code "90") (name "unconnected-(U1E-HDMI_CK_N-Pad111)") (class "Default")
      (node (ref "U1") (pin "111") (pinfunction "HDMI_CK_N_111") (pintype "passive"))
    )
    (net (code "91") (name "unconnected-(U1E-HDMI_CK_P-Pad113)") (class "Default")
      (node (ref "U1") (pin "113") (pinfunction "HDMI_CK_P_113") (pintype "passive"))
    )
    (net (code "92") (name "unconnected-(U1E-HDMI_D0_N-Pad117)") (class "Default")
      (node (ref "U1") (pin "117") (pinfunction "HDMI_D0_N_117") (pintype "passive"))
    )
    (net (code "93") (name "unconnected-(U1E-HDMI_D0_P-Pad119)") (class "Default")
      (node (ref "U1") (pin "119") (pinfunction "HDMI_D0_P_119") (pintype "passive"))
    )
    (net (code "94") (name "unconnected-(U1E-HDMI_D1_N-Pad123)") (class "Default")
      (node (ref "U1") (pin "123") (pinfunction "HDMI_D1_N_123") (pintype "passive"))
    )
    (net (code "95") (name "unconnected-(U1E-HDMI_D1_P-Pad125)") (class "Default")
      (node (ref "U1") (pin "125") (pinfunction "HDMI_D1_P_125") (pintype "passive"))
    )
    (net (code "96") (name "unconnected-(U1E-HDMI_D2_N-Pad129)") (class "Default")
      (node (ref "U1") (pin "129") (pinfunction "HDMI_D2_N_129") (pintype "passive"))
    )
    (net (code "97") (name "unconnected-(U1E-HDMI_D2_P-Pad131)") (class "Default")
      (node (ref "U1") (pin "131") (pinfunction "HDMI_D2_P_131") (pintype "passive"))
    )
    (net (code "98") (name "unconnected-(U1E-HDMI_SCL-Pad175)") (class "Default")
      (node (ref "U1") (pin "175") (pinfunction "HDMI_SCL_175") (pintype "passive"))
    )
    (net (code "99") (name "unconnected-(U1E-HDMI_SDA-Pad173)") (class "Default")
      (node (ref "U1") (pin "173") (pinfunction "HDMI_SDA_173") (pintype "passive"))
    )
    (net (code "100") (name "unconnected-(U1F-GPIO0-27_VREF-Pad39_40)") (class "Default")
      (node (ref "U1") (pin "39_40") (pinfunction "GPIO0-27_VREF_39_40") (pintype "passive"))
    )
    (net (code "101") (name "unconnected-(U1G-GPIO28-45_VREF-Pad41_42)") (class "Default")
      (node (ref "U1") (pin "41_42") (pinfunction "GPIO28-45_VREF_41_42") (pintype "passive"))
    )
    (net (code "102") (name "unconnected-(U1G-GPIO46_1V8-Pad88)") (class "Default")
      (node (ref "U1") (pin "88") (pinfunction "GPIO46_1V8_88") (pintype "passive"))
    )
    (net (code "103") (name "unconnected-(U1H-CAM1_D2_N-Pad143)") (class "Default")
      (node (ref "U1") (pin "143") (pinfunction "CAM1_D2_N_143") (pintype "passive"))
    )
    (net (code "104") (name "unconnected-(U1H-CAM1_D2_P-Pad141)") (class "Default")
      (node (ref "U1") (pin "141") (pinfunction "CAM1_D2_P_141") (pintype "passive"))
    )
    (net (code "105") (name "unconnected-(U1H-CAM1_D3_N-Pad137)") (class "Default")
      (node (ref "U1") (pin "137") (pinfunction "CAM1_D3_N_137") (pintype "passive"))
    )
    (net (code "106") (name "unconnected-(U1H-CAM1_D3_P-Pad135)") (class "Default")
      (node (ref "U1") (pin "135") (pinfunction "CAM1_D3_P_135") (pintype "passive"))
    )
    (net (code "107") (name "unconnected-(U1I-DSI0_C_N-Pad105)") (class "Default")
      (node (ref "U1") (pin "105") (pinfunction "DSI0_C_N_105") (pintype "passive"))
    )
    (net (code "108") (name "unconnected-(U1I-DSI0_C_P-Pad107)") (class "Default")
      (node (ref "U1") (pin "107") (pinfunction "DSI0_C_P_107") (pintype "passive"))
    )
    (net (code "109") (name "unconnected-(U1I-DSI0_D0_N-Pad99)") (class "Default")
      (node (ref "U1") (pin "99") (pinfunction "DSI0_D0_N_99") (pintype "passive"))
    )
    (net (code "110") (name "unconnected-(U1I-DSI0_D0_P-Pad101)") (class "Default")
      (node (ref "U1") (pin "101") (pinfunction "DSI0_D0_P_101") (pintype "passive"))
    )
    (net (code "111") (name "unconnected-(U1I-DSI0_D1_N-Pad93)") (class "Default")
      (node (ref "U1") (pin "93") (pinfunction "DSI0_D1_N_93") (pintype "passive"))
    )
    (net (code "112") (name "unconnected-(U1I-DSI0_D1_P-Pad95)") (class "Default")
      (node (ref "U1") (pin "95") (pinfunction "DSI0_D1_P_95") (pintype "passive"))
    )
    (net (code "113") (name "unconnected-(U1I-DSI1_C_N-Pad102)") (class "Default")
      (node (ref "U1") (pin "102") (pinfunction "DSI1_C_N_102") (pintype "passive"))
    )
    (net (code "114") (name "unconnected-(U1I-DSI1_C_P-Pad100)") (class "Default")
      (node (ref "U1") (pin "100") (pinfunction "DSI1_C_P_100") (pintype "passive"))
    )
    (net (code "115") (name "unconnected-(U1I-DSI1_D0_N-Pad96)") (class "Default")
      (node (ref "U1") (pin "96") (pinfunction "DSI1_D0_N_96") (pintype "passive"))
    )
    (net (code "116") (name "unconnected-(U1I-DSI1_D0_P-Pad94)") (class "Default")
      (node (ref "U1") (pin "94") (pinfunction "DSI1_D0_P_94") (pintype "passive"))
    )
    (net (code "117") (name "unconnected-(U1I-DSI1_D1_N-Pad120)") (class "Default")
      (node (ref "U1") (pin "120") (pinfunction "DSI1_D1_N_120") (pintype "passive"))
    )
    (net (code "118") (name "unconnected-(U1I-DSI1_D1_P-Pad118)") (class "Default")
      (node (ref "U1") (pin "118") (pinfunction "DSI1_D1_P_118") (pintype "passive"))
    )
    (net (code "119") (name "unconnected-(U1I-DSI1_D2_N-Pad114)") (class "Default")
      (node (ref "U1") (pin "114") (pinfunction "DSI1_D2_N_114") (pintype "passive"))
    )
    (net (code "120") (name "unconnected-(U1I-DSI1_D2_P-Pad112)") (class "Default")
      (node (ref "U1") (pin "112") (pinfunction "DSI1_D2_P_112") (pintype "passive"))
    )
    (net (code "121") (name "unconnected-(U1I-DSI1_D3_N-Pad108)") (class "Default")
      (node (ref "U1") (pin "108") (pinfunction "DSI1_D3_N_108") (pintype "passive"))
    )
    (net (code "122") (name "unconnected-(U1I-DSI1_D3_P-Pad106)") (class "Default")
      (node (ref "U1") (pin "106") (pinfunction "DSI1_D3_P_106") (pintype "passive"))
    )
    (net (code "123") (name "unconnected-(U1J-VC_TCK-Pad180)") (class "Default")
      (node (ref "U1") (pin "180") (pinfunction "VC_TCK_180") (pintype "passive"))
    )
    (net (code "124") (name "unconnected-(U1J-VC_TDI-Pad174)") (class "Default")
      (node (ref "U1") (pin "174") (pinfunction "VC_TDI_174") (pintype "passive"))
    )
    (net (code "125") (name "unconnected-(U1J-VC_TDO-Pad178)") (class "Default")
      (node (ref "U1") (pin "178") (pinfunction "VC_TDO_178") (pintype "passive"))
    )
    (net (code "126") (name "unconnected-(U1J-VC_TMS-Pad176)") (class "Default")
      (node (ref "U1") (pin "176") (pinfunction "VC_TMS_176") (pintype "passive"))
    )
    (net (code "127") (name "unconnected-(U1J-VC_TSRT_N-Pad172)") (class "Default")
      (node (ref "U1") (pin "172") (pinfunction "VC_TSRT_N_172") (pintype "passive"))
    )
    (net (code "128") (name "unconnected-(U4-NC1-Pad5)") (class "Default")
      (node (ref "U4") (pin "5") (pinfunction "NC1_5") (pintype "passive"))
    )
    (net (code "129") (name "unconnected-(U4-NC2-Pad11)") (class "Default")
      (node (ref "U4") (pin "11") (pinfunction "NC2_11") (pintype "passive"))
    )
  )
)
